# control_wdm.net
KiCad netlist of a schematic drawn in EAGLE
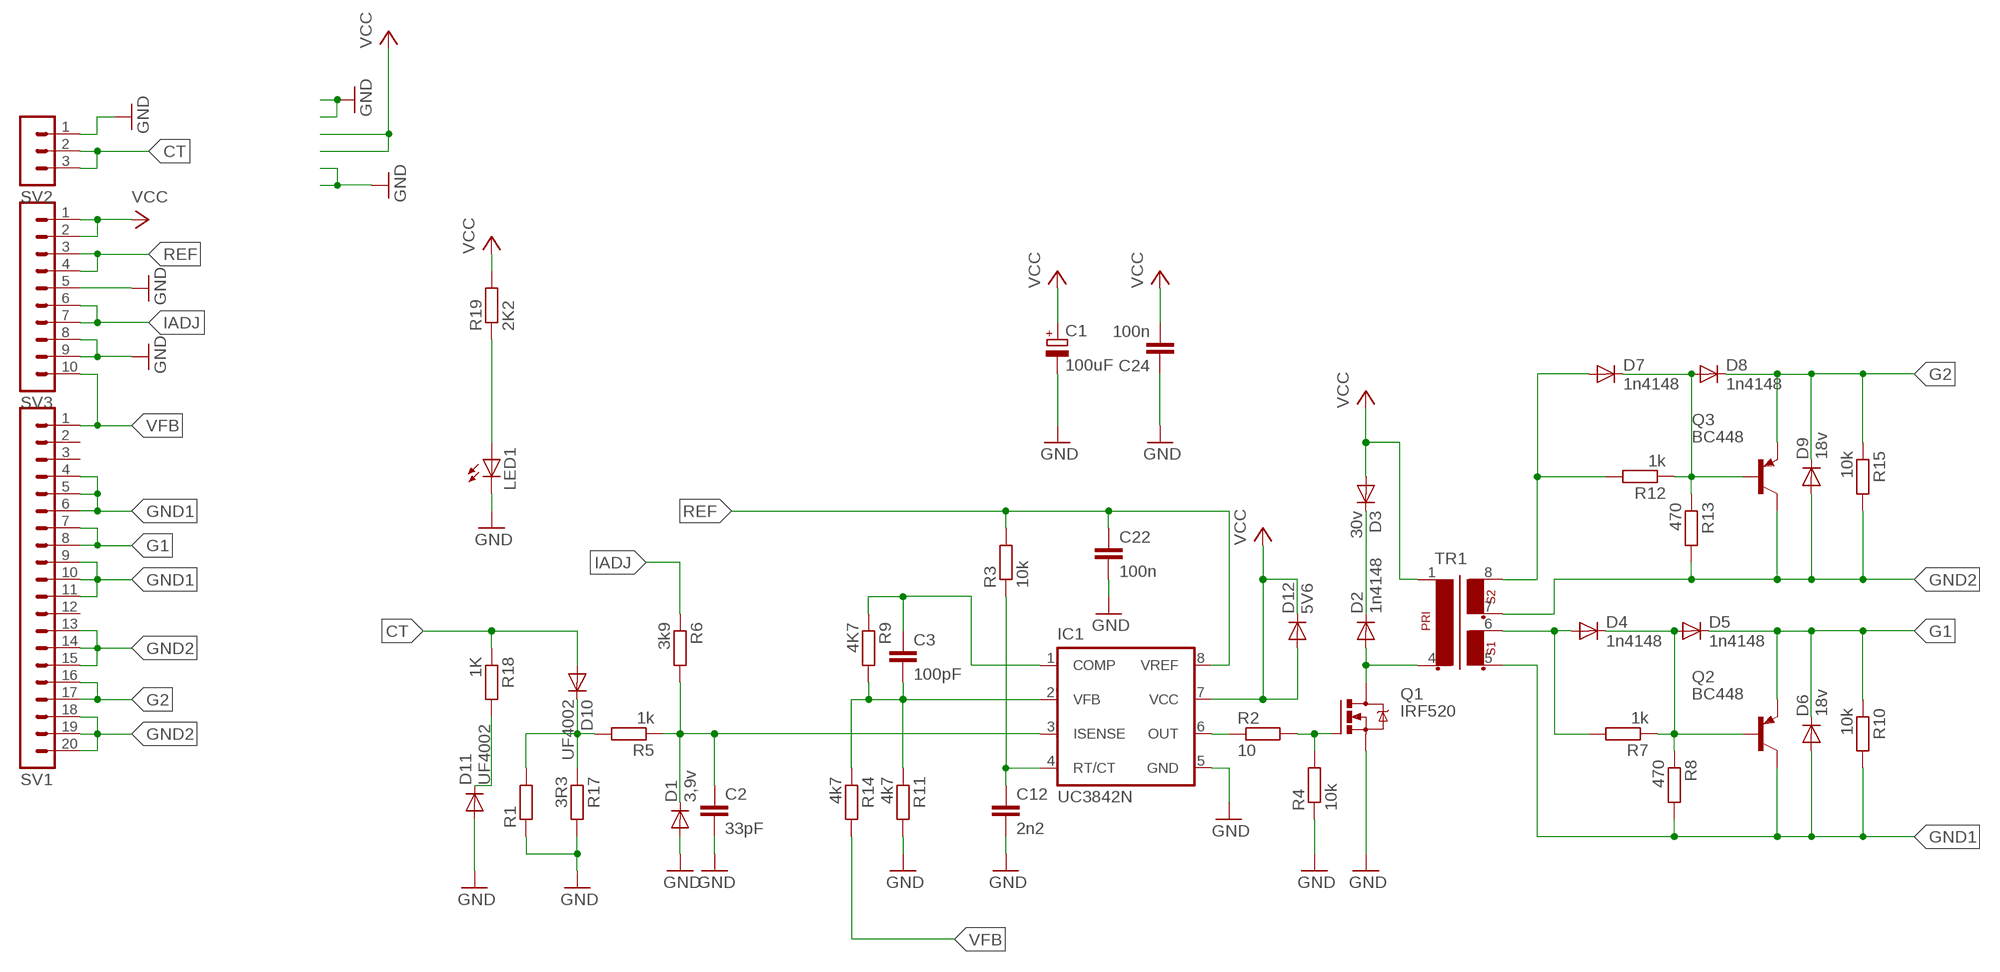
[diagram p0: schematic, sheet 1]

(export (version "E")
  (design (tool "Eeschema 10.0.6"))
  (components
    (comp (ref "C1")
      (value "100uF")
      (footprint "eagle-import:E5-6")
      (libsource (lib "eagle-import") (part "CPOL-EUE5-6"))
    )
    (comp (ref "C2")
      (value "33pF")
      (footprint "eagle-import:C050-025X075")
      (libsource (lib "eagle-import") (part "C-EU050-025X075"))
    )
    (comp (ref "C3")
      (value "100pF")
      (footprint "eagle-import:C050-025X075")
      (libsource (lib "eagle-import") (part "C-EU050-025X075"))
    )
    (comp (ref "C12")
      (value "2n2")
      (footprint "eagle-import:C050-025X075")
      (libsource (lib "eagle-import") (part "C-EU050-025X075"))
    )
    (comp (ref "C22")
      (value "100n")
      (footprint "eagle-import:C050-025X075")
      (libsource (lib "eagle-import") (part "C-EU050-025X075"))
    )
    (comp (ref "C24")
      (value "100n")
      (footprint "eagle-import:C050-025X075")
      (libsource (lib "eagle-import") (part "C-EU050-025X075"))
    )
    (comp (ref "D1")
      (value "3,9v")
      (footprint "eagle-import:DO35-10")
      (libsource (lib "eagle-import") (part "1N4446"))
    )
    (comp (ref "D2")
      (value "1n4148")
      (footprint "eagle-import:DO35-10")
      (libsource (lib "eagle-import") (part "1N4446"))
    )
    (comp (ref "D3")
      (value "30v")
      (footprint "eagle-import:DO35-10")
      (libsource (lib "eagle-import") (part "1N4446"))
    )
    (comp (ref "D4")
      (value "1n4148")
      (footprint "eagle-import:DO35-10")
      (libsource (lib "eagle-import") (part "1N4446"))
    )
    (comp (ref "D5")
      (value "1n4148")
      (footprint "eagle-import:DO35-10")
      (libsource (lib "eagle-import") (part "1N4446"))
    )
    (comp (ref "D6")
      (value "18v")
      (footprint "eagle-import:DO35-10")
      (libsource (lib "eagle-import") (part "1N4446"))
    )
    (comp (ref "D7")
      (value "1n4148")
      (footprint "eagle-import:DO35-10")
      (libsource (lib "eagle-import") (part "1N4446"))
    )
    (comp (ref "D8")
      (value "1n4148")
      (footprint "eagle-import:DO35-10")
      (libsource (lib "eagle-import") (part "1N4446"))
    )
    (comp (ref "D9")
      (value "18v")
      (footprint "eagle-import:DO35-10")
      (libsource (lib "eagle-import") (part "1N4446"))
    )
    (comp (ref "D10")
      (value "UF4002")
      (footprint "eagle-import:DO35-10")
      (libsource (lib "eagle-import") (part "1N4446"))
    )
    (comp (ref "D11")
      (value "UF4002")
      (footprint "eagle-import:DO35-10")
      (libsource (lib "eagle-import") (part "1N4446"))
    )
    (comp (ref "D12")
      (value "5V6")
      (footprint "eagle-import:DO35-10")
      (libsource (lib "eagle-import") (part "1N4446"))
    )
    (comp (ref "IC1")
      (value "UC3842N")
      (footprint "eagle-import:DIL08")
      (libsource (lib "eagle-import") (part "UC384N2"))
    )
    (comp (ref "LED1")
      (value "LED5MM")
      (footprint "eagle-import:LED5MM")
      (libsource (lib "eagle-import") (part "LED5MM"))
    )
    (comp (ref "Q1")
      (value "IRF520")
      (footprint "eagle-import:TO220BV")
      (libsource (lib "eagle-import") (part "IRF520"))
    )
    (comp (ref "Q2")
      (value "BC448")
      (footprint "eagle-import:TO92-EBC")
      (libsource (lib "eagle-import") (part "BC448"))
    )
    (comp (ref "Q3")
      (value "BC448")
      (footprint "eagle-import:TO92-EBC")
      (libsource (lib "eagle-import") (part "BC448"))
    )
    (comp (ref "R1")
      (value "R-EU_0411/12")
      (footprint "eagle-import:0411_12")
      (libsource (lib "eagle-import") (part "R-EU_0411/12"))
    )
    (comp (ref "R2")
      (value "10")
      (footprint "eagle-import:0207_10")
      (libsource (lib "eagle-import") (part "R-EU_0207/10"))
    )
    (comp (ref "R3")
      (value "10k")
      (footprint "eagle-import:0207_10")
      (libsource (lib "eagle-import") (part "R-EU_0207/10"))
    )
    (comp (ref "R4")
      (value "10k")
      (footprint "eagle-import:0207_10")
      (libsource (lib "eagle-import") (part "R-EU_0207/10"))
    )
    (comp (ref "R5")
      (value "1k")
      (footprint "eagle-import:0207_10")
      (libsource (lib "eagle-import") (part "R-EU_0207/10"))
    )
    (comp (ref "R6")
      (value "3k9")
      (footprint "eagle-import:0207_10")
      (libsource (lib "eagle-import") (part "R-EU_0207/10"))
    )
    (comp (ref "R7")
      (value "1k")
      (footprint "eagle-import:0207_10")
      (libsource (lib "eagle-import") (part "R-EU_0207/10"))
    )
    (comp (ref "R8")
      (value "470")
      (footprint "eagle-import:0207_10")
      (libsource (lib "eagle-import") (part "R-EU_0207/10"))
    )
    (comp (ref "R9")
      (value "4K7")
      (footprint "eagle-import:0207_10")
      (libsource (lib "eagle-import") (part "R-EU_0207/10"))
    )
    (comp (ref "R10")
      (value "10k")
      (footprint "eagle-import:0207_10")
      (libsource (lib "eagle-import") (part "R-EU_0207/10"))
    )
    (comp (ref "R11")
      (value "4k7")
      (footprint "eagle-import:0207_10")
      (libsource (lib "eagle-import") (part "R-EU_0207/10"))
    )
    (comp (ref "R12")
      (value "1k")
      (footprint "eagle-import:0207_10")
      (libsource (lib "eagle-import") (part "R-EU_0207/10"))
    )
    (comp (ref "R13")
      (value "470")
      (footprint "eagle-import:0207_10")
      (libsource (lib "eagle-import") (part "R-EU_0207/10"))
    )
    (comp (ref "R14")
      (value "4k7")
      (footprint "eagle-import:0207_10")
      (libsource (lib "eagle-import") (part "R-EU_0207/10"))
    )
    (comp (ref "R15")
      (value "10k")
      (footprint "eagle-import:0207_10")
      (libsource (lib "eagle-import") (part "R-EU_0207/10"))
    )
    (comp (ref "R17")
      (value "3R3")
      (footprint "eagle-import:0207_10")
      (libsource (lib "eagle-import") (part "R-EU_0207/10"))
    )
    (comp (ref "R18")
      (value "1K")
      (footprint "eagle-import:0207_10")
      (libsource (lib "eagle-import") (part "R-EU_0207/10"))
    )
    (comp (ref "R19")
      (value "2K2")
      (footprint "eagle-import:0207_10")
      (libsource (lib "eagle-import") (part "R-EU_0207/10"))
    )
    (comp (ref "SV1")
      (value "MA20-1")
      (footprint "eagle-import:MA20-1")
      (libsource (lib "eagle-import") (part "MA20-1"))
    )
    (comp (ref "SV2")
      (value "MA03-1")
      (footprint "eagle-import:MA03-1")
      (libsource (lib "eagle-import") (part "MA03-1"))
    )
    (comp (ref "SV3")
      (value "MA10-1")
      (footprint "eagle-import:MA10-1")
      (libsource (lib "eagle-import") (part "MA10-1"))
    )
    (comp (ref "TR1")
      (value "EE20-2")
      (footprint "eagle-import:EE20-2")
      (libsource (lib "eagle-import") (part "EE20-2"))
    )
  )
  (nets
    (net (code "1") (name "CT") (class "Default")
      (node (ref "D10") (pin "A") (pinfunction "A_A") (pintype "passive"))
      (node (ref "R18") (pin "1") (pinfunction "1_1") (pintype "passive"))
      (node (ref "SV2") (pin "2") (pinfunction "2_2") (pintype "passive"))
      (node (ref "SV2") (pin "3") (pinfunction "3_3") (pintype "passive"))
    )
    (net (code "2") (name "G1") (class "Default")
      (node (ref "D5") (pin "C") (pinfunction "C_C") (pintype "passive"))
      (node (ref "D6") (pin "C") (pinfunction "C_C") (pintype "passive"))
      (node (ref "Q2") (pin "E") (pinfunction "E_E") (pintype "passive"))
      (node (ref "R10") (pin "1") (pinfunction "1_1") (pintype "passive"))
      (node (ref "SV1") (pin "7") (pinfunction "7_7") (pintype "passive"))
      (node (ref "SV1") (pin "8") (pinfunction "8_8") (pintype "passive"))
    )
    (net (code "3") (name "G2") (class "Default")
      (node (ref "D8") (pin "C") (pinfunction "C_C") (pintype "passive"))
      (node (ref "D9") (pin "C") (pinfunction "C_C") (pintype "passive"))
      (node (ref "Q3") (pin "E") (pinfunction "E_E") (pintype "passive"))
      (node (ref "R15") (pin "1") (pinfunction "1_1") (pintype "passive"))
      (node (ref "SV1") (pin "16") (pinfunction "16_16") (pintype "passive"))
      (node (ref "SV1") (pin "17") (pinfunction "17_17") (pintype "passive"))
    )
    (net (code "4") (name "GND") (class "Default")
      (node (ref "C1") (pin "-") (pinfunction "-_-") (pintype "passive"))
      (node (ref "C12") (pin "2") (pinfunction "2_2") (pintype "passive"))
      (node (ref "C2") (pin "2") (pinfunction "2_2") (pintype "passive"))
      (node (ref "C22") (pin "2") (pinfunction "2_2") (pintype "passive"))
      (node (ref "C24") (pin "1") (pinfunction "1_1") (pintype "passive"))
      (node (ref "D1") (pin "A") (pinfunction "A_A") (pintype "passive"))
      (node (ref "D11") (pin "A") (pinfunction "A_A") (pintype "passive"))
      (node (ref "IC1") (pin "5") (pinfunction "GND_5") (pintype "power_in"))
      (node (ref "LED1") (pin "K") (pinfunction "C_K") (pintype "passive"))
      (node (ref "Q1") (pin "S") (pinfunction "S_S") (pintype "passive"))
      (node (ref "R1") (pin "1") (pinfunction "1_1") (pintype "passive"))
      (node (ref "R11") (pin "2") (pinfunction "2_2") (pintype "passive"))
      (node (ref "R17") (pin "2") (pinfunction "2_2") (pintype "passive"))
      (node (ref "R4") (pin "1") (pinfunction "1_1") (pintype "passive"))
      (node (ref "SV2") (pin "1") (pinfunction "1_1") (pintype "passive"))
      (node (ref "SV3") (pin "5") (pinfunction "5_5") (pintype "passive"))
      (node (ref "SV3") (pin "8") (pinfunction "8_8") (pintype "passive"))
      (node (ref "SV3") (pin "9") (pinfunction "9_9") (pintype "passive"))
    )
    (net (code "5") (name "GND1") (class "Default")
      (node (ref "D6") (pin "A") (pinfunction "A_A") (pintype "passive"))
      (node (ref "Q2") (pin "C") (pinfunction "C_C") (pintype "passive"))
      (node (ref "R10") (pin "2") (pinfunction "2_2") (pintype "passive"))
      (node (ref "R8") (pin "2") (pinfunction "2_2") (pintype "passive"))
      (node (ref "SV1") (pin "10") (pinfunction "10_10") (pintype "passive"))
      (node (ref "SV1") (pin "11") (pinfunction "11_11") (pintype "passive"))
      (node (ref "SV1") (pin "4") (pinfunction "4_4") (pintype "passive"))
      (node (ref "SV1") (pin "5") (pinfunction "5_5") (pintype "passive"))
      (node (ref "SV1") (pin "6") (pinfunction "6_6") (pintype "passive"))
      (node (ref "SV1") (pin "9") (pinfunction "9_9") (pintype "passive"))
      (node (ref "TR1") (pin "5") (pinfunction "3_5") (pintype "passive"))
    )
    (net (code "6") (name "GND2") (class "Default")
      (node (ref "D9") (pin "A") (pinfunction "A_A") (pintype "passive"))
      (node (ref "Q3") (pin "C") (pinfunction "C_C") (pintype "passive"))
      (node (ref "R13") (pin "2") (pinfunction "2_2") (pintype "passive"))
      (node (ref "R15") (pin "2") (pinfunction "2_2") (pintype "passive"))
      (node (ref "SV1") (pin "13") (pinfunction "13_13") (pintype "passive"))
      (node (ref "SV1") (pin "14") (pinfunction "14_14") (pintype "passive"))
      (node (ref "SV1") (pin "15") (pinfunction "15_15") (pintype "passive"))
      (node (ref "SV1") (pin "18") (pinfunction "18_18") (pintype "passive"))
      (node (ref "SV1") (pin "19") (pinfunction "19_19") (pintype "passive"))
      (node (ref "SV1") (pin "20") (pinfunction "20_20") (pintype "passive"))
      (node (ref "TR1") (pin "7") (pinfunction "5_7") (pintype "passive"))
    )
    (net (code "7") (name "IADJ") (class "Default")
      (node (ref "R6") (pin "1") (pinfunction "1_1") (pintype "passive"))
      (node (ref "SV3") (pin "6") (pinfunction "6_6") (pintype "passive"))
      (node (ref "SV3") (pin "7") (pinfunction "7_7") (pintype "passive"))
    )
    (net (code "8") (name "Net-(D2-PadC)") (class "Default")
      (node (ref "D2") (pin "C") (pinfunction "C_C") (pintype "passive"))
      (node (ref "D3") (pin "C") (pinfunction "C_C") (pintype "passive"))
    )
    (net (code "9") (name "Net-(D4-PadC)") (class "Default")
      (node (ref "D4") (pin "C") (pinfunction "C_C") (pintype "passive"))
      (node (ref "D5") (pin "A") (pinfunction "A_A") (pintype "passive"))
      (node (ref "Q2") (pin "B") (pinfunction "B_B") (pintype "passive"))
      (node (ref "R7") (pin "1") (pinfunction "1_1") (pintype "passive"))
      (node (ref "R8") (pin "1") (pinfunction "1_1") (pintype "passive"))
    )
    (net (code "10") (name "Net-(D7-PadC)") (class "Default")
      (node (ref "D7") (pin "C") (pinfunction "C_C") (pintype "passive"))
      (node (ref "D8") (pin "A") (pinfunction "A_A") (pintype "passive"))
      (node (ref "Q3") (pin "B") (pinfunction "B_B") (pintype "passive"))
      (node (ref "R12") (pin "1") (pinfunction "1_1") (pintype "passive"))
      (node (ref "R13") (pin "1") (pinfunction "1_1") (pintype "passive"))
    )
    (net (code "11") (name "Net-(D10-PadC)") (class "Default")
      (node (ref "D10") (pin "C") (pinfunction "C_C") (pintype "passive"))
      (node (ref "R1") (pin "2") (pinfunction "2_2") (pintype "passive"))
      (node (ref "R17") (pin "1") (pinfunction "1_1") (pintype "passive"))
      (node (ref "R5") (pin "2") (pinfunction "2_2") (pintype "passive"))
    )
    (net (code "12") (name "Net-(D11-PadC)") (class "Default")
      (node (ref "D11") (pin "C") (pinfunction "C_C") (pintype "passive"))
      (node (ref "R18") (pin "2") (pinfunction "2_2") (pintype "passive"))
    )
    (net (code "13") (name "Net-(IC1-COMP)") (class "Default")
      (node (ref "C3") (pin "1") (pinfunction "1_1") (pintype "passive"))
      (node (ref "IC1") (pin "1") (pinfunction "COMP_1") (pintype "passive"))
      (node (ref "R9") (pin "1") (pinfunction "1_1") (pintype "passive"))
    )
    (net (code "14") (name "Net-(IC1-ISENSE)") (class "Default")
      (node (ref "C2") (pin "1") (pinfunction "1_1") (pintype "passive"))
      (node (ref "D1") (pin "C") (pinfunction "C_C") (pintype "passive"))
      (node (ref "IC1") (pin "3") (pinfunction "ISENSE_3") (pintype "input"))
      (node (ref "R5") (pin "1") (pinfunction "1_1") (pintype "passive"))
      (node (ref "R6") (pin "2") (pinfunction "2_2") (pintype "passive"))
    )
    (net (code "15") (name "Net-(IC1-OUT)") (class "Default")
      (node (ref "IC1") (pin "6") (pinfunction "OUT_6") (pintype "output"))
      (node (ref "R2") (pin "1") (pinfunction "1_1") (pintype "passive"))
    )
    (net (code "16") (name "Net-(IC1-RT{slash}CT)") (class "Default")
      (node (ref "C12") (pin "1") (pinfunction "1_1") (pintype "passive"))
      (node (ref "IC1") (pin "4") (pinfunction "RT/CT_4") (pintype "passive"))
      (node (ref "R3") (pin "1") (pinfunction "1_1") (pintype "passive"))
    )
    (net (code "17") (name "Net-(IC1-VFB)") (class "Default")
      (node (ref "C3") (pin "2") (pinfunction "2_2") (pintype "passive"))
      (node (ref "IC1") (pin "2") (pinfunction "VFB_2") (pintype "input"))
      (node (ref "R11") (pin "1") (pinfunction "1_1") (pintype "passive"))
      (node (ref "R14") (pin "1") (pinfunction "1_1") (pintype "passive"))
      (node (ref "R9") (pin "2") (pinfunction "2_2") (pintype "passive"))
    )
    (net (code "18") (name "Net-(LED1-PadA)") (class "Default")
      (node (ref "LED1") (pin "A") (pinfunction "A_A") (pintype "passive"))
      (node (ref "R19") (pin "1") (pinfunction "1_1") (pintype "passive"))
    )
    (net (code "19") (name "Net-(Q1-PadG)") (class "Default")
      (node (ref "Q1") (pin "G") (pinfunction "G_G") (pintype "passive"))
      (node (ref "R2") (pin "2") (pinfunction "2_2") (pintype "passive"))
      (node (ref "R4") (pin "2") (pinfunction "2_2") (pintype "passive"))
    )
    (net (code "20") (name "Net-(TR1-2)") (class "Default")
      (node (ref "D2") (pin "A") (pinfunction "A_A") (pintype "passive"))
      (node (ref "Q1") (pin "D") (pinfunction "D_D") (pintype "passive"))
      (node (ref "TR1") (pin "4") (pinfunction "2_4") (pintype "passive"))
    )
    (net (code "21") (name "Net-(TR1-4)") (class "Default")
      (node (ref "D4") (pin "A") (pinfunction "A_A") (pintype "passive"))
      (node (ref "R7") (pin "2") (pinfunction "2_2") (pintype "passive"))
      (node (ref "TR1") (pin "6") (pinfunction "4_6") (pintype "passive"))
    )
    (net (code "22") (name "Net-(TR1-6)") (class "Default")
      (node (ref "D7") (pin "A") (pinfunction "A_A") (pintype "passive"))
      (node (ref "R12") (pin "2") (pinfunction "2_2") (pintype "passive"))
      (node (ref "TR1") (pin "8") (pinfunction "6_8") (pintype "passive"))
    )
    (net (code "23") (name "REF") (class "Default")
      (node (ref "C22") (pin "1") (pinfunction "1_1") (pintype "passive"))
      (node (ref "IC1") (pin "8") (pinfunction "VREF_8") (pintype "passive"))
      (node (ref "R3") (pin "2") (pinfunction "2_2") (pintype "passive"))
      (node (ref "SV3") (pin "3") (pinfunction "3_3") (pintype "passive"))
      (node (ref "SV3") (pin "4") (pinfunction "4_4") (pintype "passive"))
    )
    (net (code "24") (name "VCC") (class "Default")
      (node (ref "C1") (pin "+") (pinfunction "+_+") (pintype "passive"))
      (node (ref "C24") (pin "2") (pinfunction "2_2") (pintype "passive"))
      (node (ref "D12") (pin "A") (pinfunction "A_A") (pintype "passive"))
      (node (ref "D12") (pin "C") (pinfunction "C_C") (pintype "passive"))
      (node (ref "D3") (pin "A") (pinfunction "A_A") (pintype "passive"))
      (node (ref "IC1") (pin "7") (pinfunction "VCC_7") (pintype "power_in"))
      (node (ref "R19") (pin "2") (pinfunction "2_2") (pintype "passive"))
      (node (ref "SV3") (pin "1") (pinfunction "1_1") (pintype "passive"))
      (node (ref "SV3") (pin "2") (pinfunction "2_2") (pintype "passive"))
      (node (ref "TR1") (pin "1") (pinfunction "1_1") (pintype "passive"))
    )
    (net (code "25") (name "VFB") (class "Default")
      (node (ref "R14") (pin "2") (pinfunction "2_2") (pintype "passive"))
      (node (ref "SV1") (pin "1") (pinfunction "1_1") (pintype "passive"))
      (node (ref "SV3") (pin "10") (pinfunction "10_10") (pintype "passive"))
    )
    (net (code "26") (name "unconnected-(SV1-Pad2)") (class "Default")
      (node (ref "SV1") (pin "2") (pinfunction "2_2") (pintype "passive"))
    )
    (net (code "27") (name "unconnected-(SV1-Pad3)") (class "Default")
      (node (ref "SV1") (pin "3") (pinfunction "3_3") (pintype "passive"))
    )
    (net (code "28") (name "unconnected-(SV1-Pad12)") (class "Default")
      (node (ref "SV1") (pin "12") (pinfunction "12_12") (pintype "passive"))
    )
  )
)
